# gydrodrive_mcu.net
KiCad netlist of a schematic drawn in Altium Designer
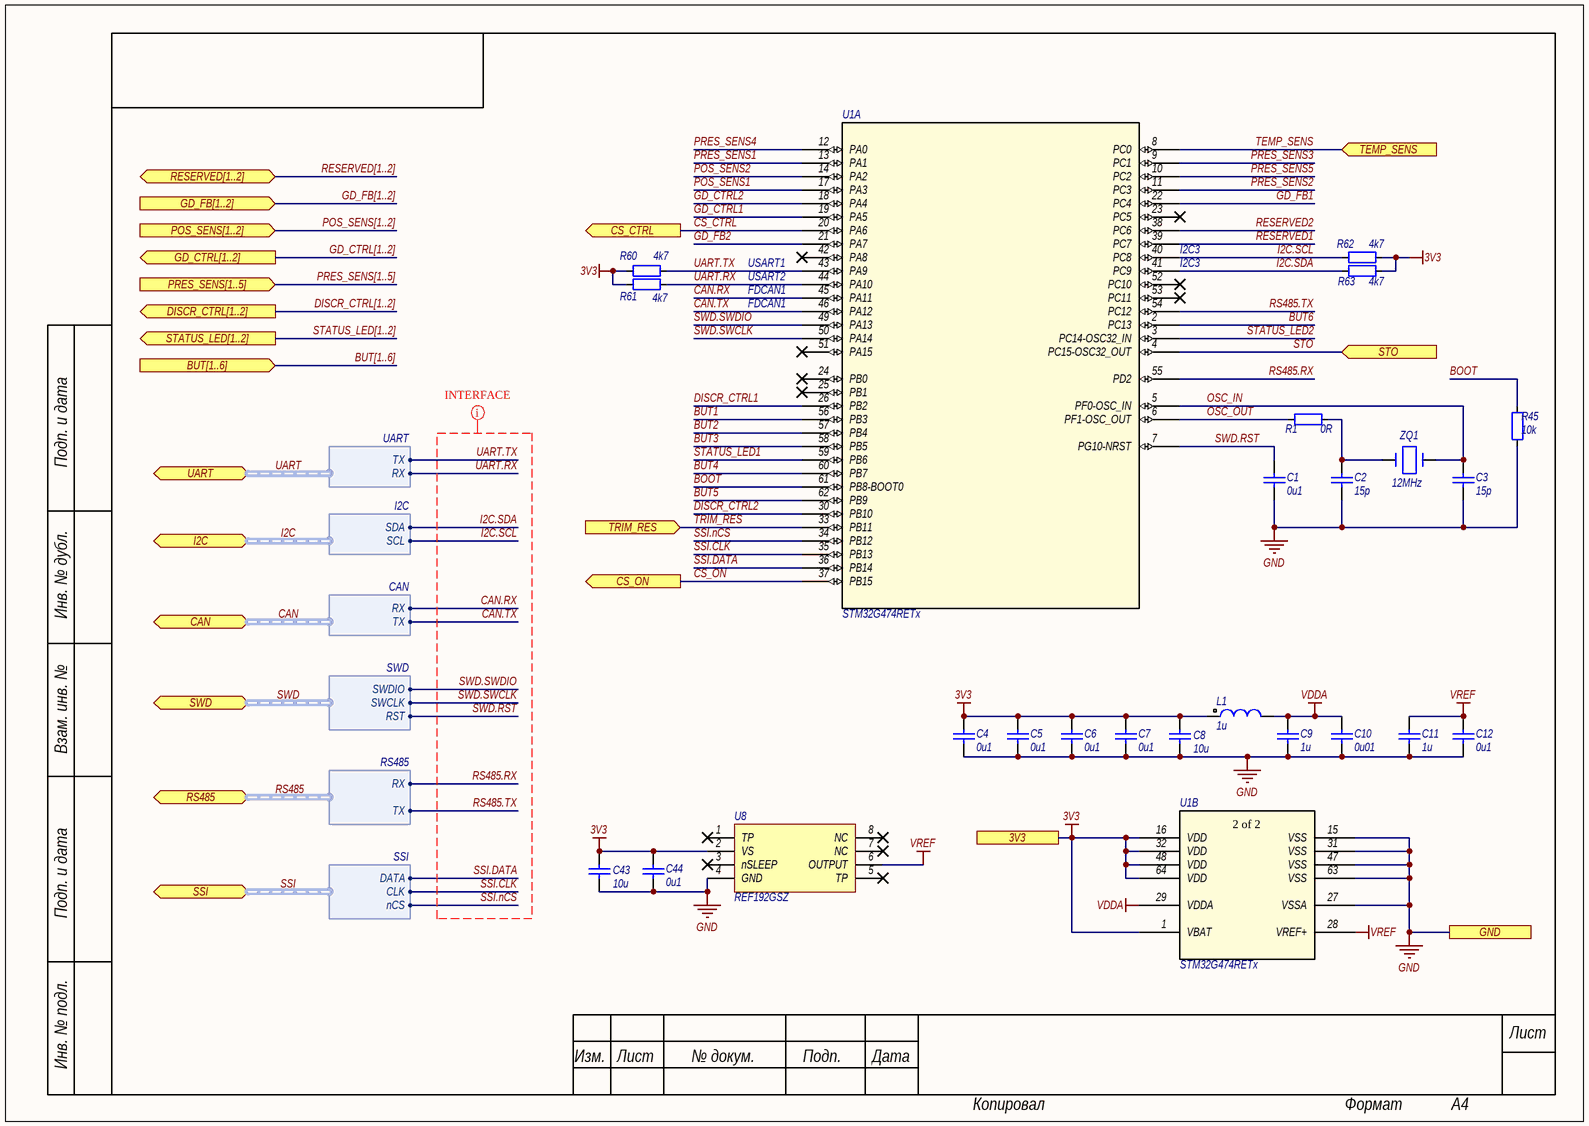
[diagram p0: gydrodrive_mcu.SchDoc]

(export (version "E")
  (design (tool "Eeschema 10.0.6"))
  (components
    (comp (ref "C1")
      (value "CAP_0805")
      (footprint "CAPC2012-0805M")
      (description "Конденсатор керамический, корпус 0805")
      (fields
        (field (name "CAPACITANCE") "0u1")
        (field (name "PART NUMBER") "CAPC_0805")
        (field (name "VOLTAGE") "50V")
      )
      (libsource (lib "StdLib") (part "CAP"))
    )
    (comp (ref "C2")
      (value "CAP_0805")
      (footprint "CAPC2012-0805M")
      (description "Конденсатор керамический, корпус 0805")
      (fields
        (field (name "CAPACITANCE") "15p")
        (field (name "PART NUMBER") "CAPC_0805")
        (field (name "VOLTAGE") "50V")
      )
      (libsource (lib "StdLib") (part "CAP"))
    )
    (comp (ref "C3")
      (value "CAP_0805")
      (footprint "CAPC2012-0805M")
      (description "Конденсатор керамический, корпус 0805")
      (fields
        (field (name "CAPACITANCE") "15p")
        (field (name "PART NUMBER") "CAPC_0805")
        (field (name "VOLTAGE") "50V")
      )
      (libsource (lib "StdLib") (part "CAP"))
    )
    (comp (ref "C4")
      (value "CAP_0805")
      (footprint "CAPC2012-0805M")
      (description "Конденсатор керамический, корпус 0805")
      (fields
        (field (name "CAPACITANCE") "0u1")
        (field (name "PART NUMBER") "CAPC_0805")
        (field (name "VOLTAGE") "50V")
      )
      (libsource (lib "StdLib") (part "CAP"))
    )
    (comp (ref "C5")
      (value "CAP_0805")
      (footprint "CAPC2012-0805M")
      (description "Конденсатор керамический, корпус 0805")
      (fields
        (field (name "CAPACITANCE") "0u1")
        (field (name "PART NUMBER") "CAPC_0805")
        (field (name "VOLTAGE") "50V")
      )
      (libsource (lib "StdLib") (part "CAP"))
    )
    (comp (ref "C6")
      (value "CAP_0805")
      (footprint "CAPC2012-0805M")
      (description "Конденсатор керамический, корпус 0805")
      (fields
        (field (name "CAPACITANCE") "0u1")
        (field (name "PART NUMBER") "CAPC_0805")
        (field (name "VOLTAGE") "50V")
      )
      (libsource (lib "StdLib") (part "CAP"))
    )
    (comp (ref "C7")
      (value "CAP_0805")
      (footprint "CAPC2012-0805M")
      (description "Конденсатор керамический, корпус 0805")
      (fields
        (field (name "CAPACITANCE") "0u1")
        (field (name "PART NUMBER") "CAPC_0805")
        (field (name "VOLTAGE") "50V")
      )
      (libsource (lib "StdLib") (part "CAP"))
    )
    (comp (ref "C8")
      (value "CAP_0805")
      (footprint "CAPC2012-0805M")
      (description "Конденсатор керамический, корпус 0805")
      (fields
        (field (name "CAPACITANCE") "10u")
        (field (name "PART NUMBER") "CAPC_0805")
        (field (name "VOLTAGE") "16V")
      )
      (libsource (lib "StdLib") (part "CAP"))
    )
    (comp (ref "C9")
      (value "CAP_0805")
      (footprint "CAPC2012-0805M")
      (description "Конденсатор керамический, корпус 0805")
      (fields
        (field (name "CAPACITANCE") "1u")
        (field (name "PART NUMBER") "CAPC_0805")
        (field (name "VOLTAGE") "50V")
      )
      (libsource (lib "StdLib") (part "CAP"))
    )
    (comp (ref "C10")
      (value "CAP_0805")
      (footprint "CAPC2012-0805M")
      (description "Конденсатор керамический, корпус 0805")
      (fields
        (field (name "CAPACITANCE") "0u01")
        (field (name "PART NUMBER") "CAPC_0805")
        (field (name "VOLTAGE") "50V")
      )
      (libsource (lib "StdLib") (part "CAP"))
    )
    (comp (ref "C11")
      (value "CAP_0805")
      (footprint "CAPC2012-0805M")
      (description "Конденсатор керамический, корпус 0805")
      (fields
        (field (name "CAPACITANCE") "1u")
        (field (name "PART NUMBER") "CAPC_0805")
        (field (name "VOLTAGE") "50V")
      )
      (libsource (lib "StdLib") (part "CAP"))
    )
    (comp (ref "C12")
      (value "CAP_0805")
      (footprint "CAPC2012-0805M")
      (description "Конденсатор керамический, корпус 0805")
      (fields
        (field (name "CAPACITANCE") "0u1")
        (field (name "PART NUMBER") "CAPC_0805")
        (field (name "VOLTAGE") "50V")
      )
      (libsource (lib "StdLib") (part "CAP"))
    )
    (comp (ref "C43")
      (value "CAP_0805")
      (footprint "CAPC2012-0805M")
      (description "Конденсатор керамический, корпус 0805")
      (fields
        (field (name "CAPACITANCE") "10u")
        (field (name "PART NUMBER") "CAPC_0805")
        (field (name "VOLTAGE") "16V")
      )
      (libsource (lib "StdLib") (part "CAP"))
    )
    (comp (ref "C44")
      (value "CAP_0805")
      (footprint "CAPC2012-0805M")
      (description "Конденсатор керамический, корпус 0805")
      (fields
        (field (name "CAPACITANCE") "0u1")
        (field (name "PART NUMBER") "CAPC_0805")
        (field (name "VOLTAGE") "50V")
      )
      (libsource (lib "StdLib") (part "CAP"))
    )
    (comp (ref "L1")
      (value "IND_0805")
      (footprint "INDC2012-0805M")
      (description "Индуктивность, корпус 0805")
      (fields (field (name "INDUCTANCE") "1u") (field (name "PART NUMBER") "INDC_0805"))
      (libsource (lib "StdLib") (part "IND"))
    )
    (comp (ref "R1")
      (value "RES_0805")
      (footprint "RESC2012-0805M")
      (description "Рез-р, корпус 0805")
      (fields
        (field (name "RESISTANCE") "0R")
        (field (name "PART NUMBER") "RESC_0805")
        (field (name "TOLERANCE") "5%")
      )
      (libsource (lib "") (part "RES_2"))
    )
    (comp (ref "R45")
      (value "RES_0805")
      (footprint "RESC2012-0805M")
      (description "Рез-р, корпус 0805")
      (fields
        (field (name "RESISTANCE") "10k")
        (field (name "PART NUMBER") "RESC_0805")
        (field (name "TOLERANCE") "5%")
      )
      (libsource (lib "") (part "RES_1"))
    )
    (comp (ref "R60")
      (value "RES_0805")
      (footprint "RESC2012-0805M")
      (description "Рез-р, корпус 0805")
      (fields
        (field (name "RESISTANCE") "4k7")
        (field (name "PART NUMBER") "RESC_0805")
        (field (name "TOLERANCE") "5%")
      )
      (libsource (lib "StdLib") (part "RES"))
    )
    (comp (ref "R61")
      (value "RES_0805")
      (footprint "RESC2012-0805M")
      (description "Рез-р, корпус 0805")
      (fields
        (field (name "RESISTANCE") "4k7")
        (field (name "PART NUMBER") "RESC_0805")
        (field (name "TOLERANCE") "5%")
      )
      (libsource (lib "StdLib") (part "RES"))
    )
    (comp (ref "R62")
      (value "RES_0805")
      (footprint "RESC2012-0805M")
      (description "Рез-р, корпус 0805")
      (fields
        (field (name "RESISTANCE") "4k7")
        (field (name "PART NUMBER") "RESC_0805")
        (field (name "TOLERANCE") "5%")
      )
      (libsource (lib "StdLib") (part "RES"))
    )
    (comp (ref "R63")
      (value "RES_0805")
      (footprint "RESC2012-0805M")
      (description "Рез-р, корпус 0805")
      (fields
        (field (name "RESISTANCE") "4k7")
        (field (name "PART NUMBER") "RESC_0805")
        (field (name "TOLERANCE") "5%")
      )
      (libsource (lib "StdLib") (part "RES"))
    )
    (comp (ref "U1")
      (value "STM32G474RETx")
      (footprint "LQFP50P1200X1200X160-64M")
      (fields
        (field (name "MANUFACTURER_PART_NUMBER") "stm32g4_lqfp64_t1")
        (field (name "COPYRIGHT") "Copyright (C) 2016 Accelerated Designs. All rights reserved")
      )
      (libsource (lib "ST Microelectronics STM32 G4") (part "STM32G474RETx"))
    )
    (comp (ref "U8")
      (value "REF192GSZ")
      (footprint "SO8_M")
      (description "Источник опорного напряжения, 2.5 В")
      (fields (field (name "VOLTAGE") "2.5V") (field (name "TOLERANCE") "0.4%"))
      (libsource (lib "StdLib") (part "REF19x"))
    )
    (comp (ref "ZQ1")
      (value "QRZ_HC_49_SMD")
      (footprint "HC-49SMD")
      (description "Кварцевый резонатор в корпусе HC-49 SMD")
      (fields (field (name "PARAMETERS") "12MHz"))
      (libsource (lib "StdLib") (part "QRZ HC49"))
    )
  )
  (nets
    (net (code "7") (name "/BOOT") (class "Default")
      (node (ref "R45") (pin "2") (pinfunction "2_2") (pintype "passive"))
      (node (ref "U1") (pin "61") (pinfunction "PB8-BOOT0_61") (pintype "bidirectional"))
    )
    (net (code "8") (name "/BUT1") (class "Default")
      (node (ref "U1") (pin "56") (pinfunction "PB3_56") (pintype "bidirectional"))
    )
    (net (code "9") (name "/BUT2") (class "Default")
      (node (ref "U1") (pin "57") (pinfunction "PB4_57") (pintype "bidirectional"))
    )
    (net (code "10") (name "/BUT3") (class "Default")
      (node (ref "U1") (pin "58") (pinfunction "PB5_58") (pintype "bidirectional"))
    )
    (net (code "11") (name "/BUT4") (class "Default")
      (node (ref "U1") (pin "60") (pinfunction "PB7_60") (pintype "bidirectional"))
    )
    (net (code "12") (name "/BUT5") (class "Default")
      (node (ref "U1") (pin "62") (pinfunction "PB9_62") (pintype "bidirectional"))
    )
    (net (code "13") (name "/BUT6") (class "Default")
      (node (ref "U1") (pin "2") (pinfunction "PC13_2") (pintype "bidirectional"))
    )
    (net (code "15") (name "/CAN.RX") (class "Default")
      (node (ref "U1") (pin "45") (pinfunction "PA11_45") (pintype "bidirectional"))
    )
    (net (code "16") (name "/CAN.TX") (class "Default")
      (node (ref "U1") (pin "46") (pinfunction "PA12_46") (pintype "bidirectional"))
    )
    (net (code "18") (name "/CS_CTRL") (class "Default")
      (node (ref "U1") (pin "20") (pinfunction "PA6_20") (pintype "bidirectional"))
    )
    (net (code "19") (name "/CS_ON") (class "Default")
      (node (ref "U1") (pin "37") (pinfunction "PB15_37") (pintype "bidirectional"))
    )
    (net (code "20") (name "/DISCR_CTRL1") (class "Default")
      (node (ref "U1") (pin "26") (pinfunction "PB2_26") (pintype "bidirectional"))
    )
    (net (code "21") (name "/DISCR_CTRL2") (class "Default")
      (node (ref "U1") (pin "30") (pinfunction "PB10_30") (pintype "bidirectional"))
    )
    (net (code "23") (name "/GD_CTRL1") (class "Default")
      (node (ref "U1") (pin "19") (pinfunction "PA5_19") (pintype "bidirectional"))
    )
    (net (code "24") (name "/GD_CTRL2") (class "Default")
      (node (ref "U1") (pin "18") (pinfunction "PA4_18") (pintype "bidirectional"))
    )
    (net (code "26") (name "/GD_FB1") (class "Default")
      (node (ref "U1") (pin "22") (pinfunction "PC4_22") (pintype "bidirectional"))
    )
    (net (code "27") (name "/GD_FB2") (class "Default")
      (node (ref "U1") (pin "21") (pinfunction "PA7_21") (pintype "bidirectional"))
    )
    (net (code "29") (name "/I2C.SCL") (class "Default")
      (node (ref "R62") (pin "2") (pinfunction "2_2") (pintype "passive"))
      (node (ref "U1") (pin "40") (pinfunction "PC8_40") (pintype "bidirectional"))
    )
    (net (code "30") (name "/I2C.SDA") (class "Default")
      (node (ref "R63") (pin "2") (pinfunction "2_2") (pintype "passive"))
      (node (ref "U1") (pin "41") (pinfunction "PC9_41") (pintype "bidirectional"))
    )
    (net (code "32") (name "/OSC_IN") (class "Default")
      (node (ref "C3") (pin "2") (pinfunction "2_2") (pintype "passive"))
      (node (ref "U1") (pin "5") (pinfunction "PF0-OSC_IN_5") (pintype "bidirectional"))
      (node (ref "ZQ1") (pin "2") (pinfunction "2_2") (pintype "passive"))
    )
    (net (code "33") (name "/OSC_OUT") (class "Default")
      (node (ref "R1") (pin "1") (pinfunction "1_1") (pintype "passive"))
      (node (ref "U1") (pin "6") (pinfunction "PF1-OSC_OUT_6") (pintype "bidirectional"))
    )
    (net (code "34") (name "/POS_SENS1") (class "Default")
      (node (ref "U1") (pin "17") (pinfunction "PA3_17") (pintype "bidirectional"))
    )
    (net (code "35") (name "/POS_SENS2") (class "Default")
      (node (ref "U1") (pin "14") (pinfunction "PA2_14") (pintype "bidirectional"))
    )
    (net (code "37") (name "/PRES_SENS1") (class "Default")
      (node (ref "U1") (pin "13") (pinfunction "PA1_13") (pintype "bidirectional"))
    )
    (net (code "38") (name "/PRES_SENS2") (class "Default")
      (node (ref "U1") (pin "11") (pinfunction "PC3_11") (pintype "bidirectional"))
    )
    (net (code "39") (name "/PRES_SENS3") (class "Default")
      (node (ref "U1") (pin "9") (pinfunction "PC1_9") (pintype "bidirectional"))
    )
    (net (code "40") (name "/PRES_SENS4") (class "Default")
      (node (ref "U1") (pin "12") (pinfunction "PA0_12") (pintype "bidirectional"))
    )
    (net (code "41") (name "/PRES_SENS5") (class "Default")
      (node (ref "U1") (pin "10") (pinfunction "PC2_10") (pintype "bidirectional"))
    )
    (net (code "43") (name "/RESERVED1") (class "Default")
      (node (ref "U1") (pin "39") (pinfunction "PC7_39") (pintype "bidirectional"))
    )
    (net (code "44") (name "/RESERVED2") (class "Default")
      (node (ref "U1") (pin "38") (pinfunction "PC6_38") (pintype "bidirectional"))
    )
    (net (code "46") (name "/RS485.RX") (class "Default")
      (node (ref "U1") (pin "55") (pinfunction "PD2_55") (pintype "bidirectional"))
    )
    (net (code "47") (name "/RS485.TX") (class "Default")
      (node (ref "U1") (pin "54") (pinfunction "PC12_54") (pintype "bidirectional"))
    )
    (net (code "49") (name "/SSI.CLK") (class "Default")
      (node (ref "U1") (pin "35") (pinfunction "PB13_35") (pintype "bidirectional"))
    )
    (net (code "50") (name "/SSI.DATA") (class "Default")
      (node (ref "U1") (pin "36") (pinfunction "PB14_36") (pintype "bidirectional"))
    )
    (net (code "51") (name "/SSI.nCS") (class "Default")
      (node (ref "U1") (pin "34") (pinfunction "PB12_34") (pintype "bidirectional"))
    )
    (net (code "53") (name "/STATUS_LED1") (class "Default")
      (node (ref "U1") (pin "59") (pinfunction "PB6_59") (pintype "bidirectional"))
    )
    (net (code "54") (name "/STATUS_LED2") (class "Default")
      (node (ref "U1") (pin "3") (pinfunction "PC14-OSC32_IN_3") (pintype "bidirectional"))
    )
    (net (code "56") (name "/STO") (class "Default")
      (node (ref "U1") (pin "4") (pinfunction "PC15-OSC32_OUT_4") (pintype "bidirectional"))
    )
    (net (code "57") (name "/SWD.RST") (class "Default")
      (node (ref "C1") (pin "2") (pinfunction "2_2") (pintype "passive"))
      (node (ref "U1") (pin "7") (pinfunction "PG10-NRST_7") (pintype "bidirectional"))
    )
    (net (code "58") (name "/SWD.SWCLK") (class "Default")
      (node (ref "U1") (pin "50") (pinfunction "PA14_50") (pintype "bidirectional"))
    )
    (net (code "59") (name "/SWD.SWDIO") (class "Default")
      (node (ref "U1") (pin "49") (pinfunction "PA13_49") (pintype "bidirectional"))
    )
    (net (code "61") (name "/TEMP_SENS") (class "Default")
      (node (ref "U1") (pin "8") (pinfunction "PC0_8") (pintype "bidirectional"))
    )
    (net (code "62") (name "/TRIM_RES") (class "Default")
      (node (ref "U1") (pin "33") (pinfunction "PB11_33") (pintype "bidirectional"))
    )
    (net (code "63") (name "/UART.RX") (class "Default")
      (node (ref "R61") (pin "1") (pinfunction "1_1") (pintype "passive"))
      (node (ref "U1") (pin "44") (pinfunction "PA10_44") (pintype "bidirectional"))
    )
    (net (code "64") (name "/UART.TX") (class "Default")
      (node (ref "R60") (pin "1") (pinfunction "1_1") (pintype "passive"))
      (node (ref "U1") (pin "43") (pinfunction "PA9_43") (pintype "bidirectional"))
    )
    (net (code "66") (name "3V3") (class "Default")
      (node (ref "C4") (pin "2") (pinfunction "2_2") (pintype "passive"))
      (node (ref "C43") (pin "2") (pinfunction "2_2") (pintype "passive"))
      (node (ref "C44") (pin "2") (pinfunction "2_2") (pintype "passive"))
      (node (ref "C5") (pin "2") (pinfunction "2_2") (pintype "passive"))
      (node (ref "C6") (pin "2") (pinfunction "2_2") (pintype "passive"))
      (node (ref "C7") (pin "2") (pinfunction "2_2") (pintype "passive"))
      (node (ref "C8") (pin "2") (pinfunction "2_2") (pintype "passive"))
      (node (ref "L1") (pin "1") (pinfunction "1_1") (pintype "passive"))
      (node (ref "R60") (pin "2") (pinfunction "2_2") (pintype "passive"))
      (node (ref "R61") (pin "2") (pinfunction "2_2") (pintype "passive"))
      (node (ref "R62") (pin "1") (pinfunction "1_1") (pintype "passive"))
      (node (ref "R63") (pin "1") (pinfunction "1_1") (pintype "passive"))
      (node (ref "U1") (pin "1") (pinfunction "VBAT_1") (pintype "power_in"))
      (node (ref "U1") (pin "16") (pinfunction "VDD_16") (pintype "power_in"))
      (node (ref "U1") (pin "32") (pinfunction "VDD_32") (pintype "power_in"))
      (node (ref "U1") (pin "48") (pinfunction "VDD_48") (pintype "power_in"))
      (node (ref "U1") (pin "64") (pinfunction "VDD_64") (pintype "power_in"))
      (node (ref "U8") (pin "2") (pinfunction "VS_2") (pintype "passive"))
    )
    (net (code "67") (name "GND") (class "Default")
      (node (ref "C1") (pin "1") (pinfunction "1_1") (pintype "passive"))
      (node (ref "C10") (pin "1") (pinfunction "1_1") (pintype "passive"))
      (node (ref "C11") (pin "1") (pinfunction "1_1") (pintype "passive"))
      (node (ref "C12") (pin "1") (pinfunction "1_1") (pintype "passive"))
      (node (ref "C2") (pin "1") (pinfunction "1_1") (pintype "passive"))
      (node (ref "C3") (pin "1") (pinfunction "1_1") (pintype "passive"))
      (node (ref "C4") (pin "1") (pinfunction "1_1") (pintype "passive"))
      (node (ref "C43") (pin "1") (pinfunction "1_1") (pintype "passive"))
      (node (ref "C44") (pin "1") (pinfunction "1_1") (pintype "passive"))
      (node (ref "C5") (pin "1") (pinfunction "1_1") (pintype "passive"))
      (node (ref "C6") (pin "1") (pinfunction "1_1") (pintype "passive"))
      (node (ref "C7") (pin "1") (pinfunction "1_1") (pintype "passive"))
      (node (ref "C8") (pin "1") (pinfunction "1_1") (pintype "passive"))
      (node (ref "C9") (pin "1") (pinfunction "1_1") (pintype "passive"))
      (node (ref "R45") (pin "1") (pinfunction "1_1") (pintype "passive"))
      (node (ref "U1") (pin "15") (pinfunction "VSS_15") (pintype "power_in"))
      (node (ref "U1") (pin "27") (pinfunction "VSSA_27") (pintype "power_in"))
      (node (ref "U1") (pin "31") (pinfunction "VSS_31") (pintype "power_in"))
      (node (ref "U1") (pin "47") (pinfunction "VSS_47") (pintype "power_in"))
      (node (ref "U1") (pin "63") (pinfunction "VSS_63") (pintype "power_in"))
      (node (ref "U8") (pin "4") (pinfunction "GND_4") (pintype "passive"))
    )
    (net (code "68") (name "Net-(C2-Pad2)") (class "Default")
      (node (ref "C2") (pin "2") (pinfunction "2_2") (pintype "passive"))
      (node (ref "R1") (pin "2") (pinfunction "2_2") (pintype "passive"))
      (node (ref "ZQ1") (pin "1") (pinfunction "1_1") (pintype "passive"))
    )
    (net (code "69") (name "VDDA") (class "Default")
      (node (ref "C10") (pin "2") (pinfunction "2_2") (pintype "passive"))
      (node (ref "C9") (pin "2") (pinfunction "2_2") (pintype "passive"))
      (node (ref "L1") (pin "2") (pinfunction "2_2") (pintype "passive"))
      (node (ref "U1") (pin "29") (pinfunction "VDDA_29") (pintype "power_in"))
    )
    (net (code "70") (name "VREF") (class "Default")
      (node (ref "C11") (pin "2") (pinfunction "2_2") (pintype "passive"))
      (node (ref "C12") (pin "2") (pinfunction "2_2") (pintype "passive"))
      (node (ref "U1") (pin "28") (pinfunction "VREF+_28") (pintype "power_in"))
      (node (ref "U8") (pin "6") (pinfunction "OUTPUT_6") (pintype "passive"))
    )
    (net (code "71") (name "unconnected-(U1A-PA8-Pad42)") (class "Default")
      (node (ref "U1") (pin "42") (pinfunction "PA8_42") (pintype "bidirectional+no_connect"))
    )
    (net (code "72") (name "unconnected-(U1A-PA15-Pad51)") (class "Default")
      (node (ref "U1") (pin "51") (pinfunction "PA15_51") (pintype "bidirectional+no_connect"))
    )
    (net (code "73") (name "unconnected-(U1A-PB0-Pad24)") (class "Default")
      (node (ref "U1") (pin "24") (pinfunction "PB0_24") (pintype "bidirectional+no_connect"))
    )
    (net (code "74") (name "unconnected-(U1A-PB1-Pad25)") (class "Default")
      (node (ref "U1") (pin "25") (pinfunction "PB1_25") (pintype "bidirectional+no_connect"))
    )
    (net (code "75") (name "unconnected-(U1A-PC5-Pad23)") (class "Default")
      (node (ref "U1") (pin "23") (pinfunction "PC5_23") (pintype "bidirectional+no_connect"))
    )
    (net (code "76") (name "unconnected-(U1A-PC10-Pad52)") (class "Default")
      (node (ref "U1") (pin "52") (pinfunction "PC10_52") (pintype "bidirectional+no_connect"))
    )
    (net (code "77") (name "unconnected-(U1A-PC11-Pad53)") (class "Default")
      (node (ref "U1") (pin "53") (pinfunction "PC11_53") (pintype "bidirectional+no_connect"))
    )
    (net (code "78") (name "unconnected-(U8-NC-Pad7)") (class "Default")
      (node (ref "U8") (pin "7") (pinfunction "NC_7") (pintype "passive+no_connect"))
    )
    (net (code "79") (name "unconnected-(U8-NC-Pad8)") (class "Default")
      (node (ref "U8") (pin "8") (pinfunction "NC_8") (pintype "passive+no_connect"))
    )
    (net (code "80") (name "unconnected-(U8-TP-Pad1)") (class "Default")
      (node (ref "U8") (pin "1") (pinfunction "TP_1") (pintype "passive+no_connect"))
    )
    (net (code "81") (name "unconnected-(U8-TP-Pad5)") (class "Default")
      (node (ref "U8") (pin "5") (pinfunction "TP_5") (pintype "passive+no_connect"))
    )
    (net (code "82") (name "unconnected-(U8-nSLEEP-Pad3)") (class "Default")
      (node (ref "U8") (pin "3") (pinfunction "nSLEEP_3") (pintype "passive+no_connect"))
    )
  )
)
